# Pump_shield.net
KiCad netlist of a schematic drawn in Altium Designer
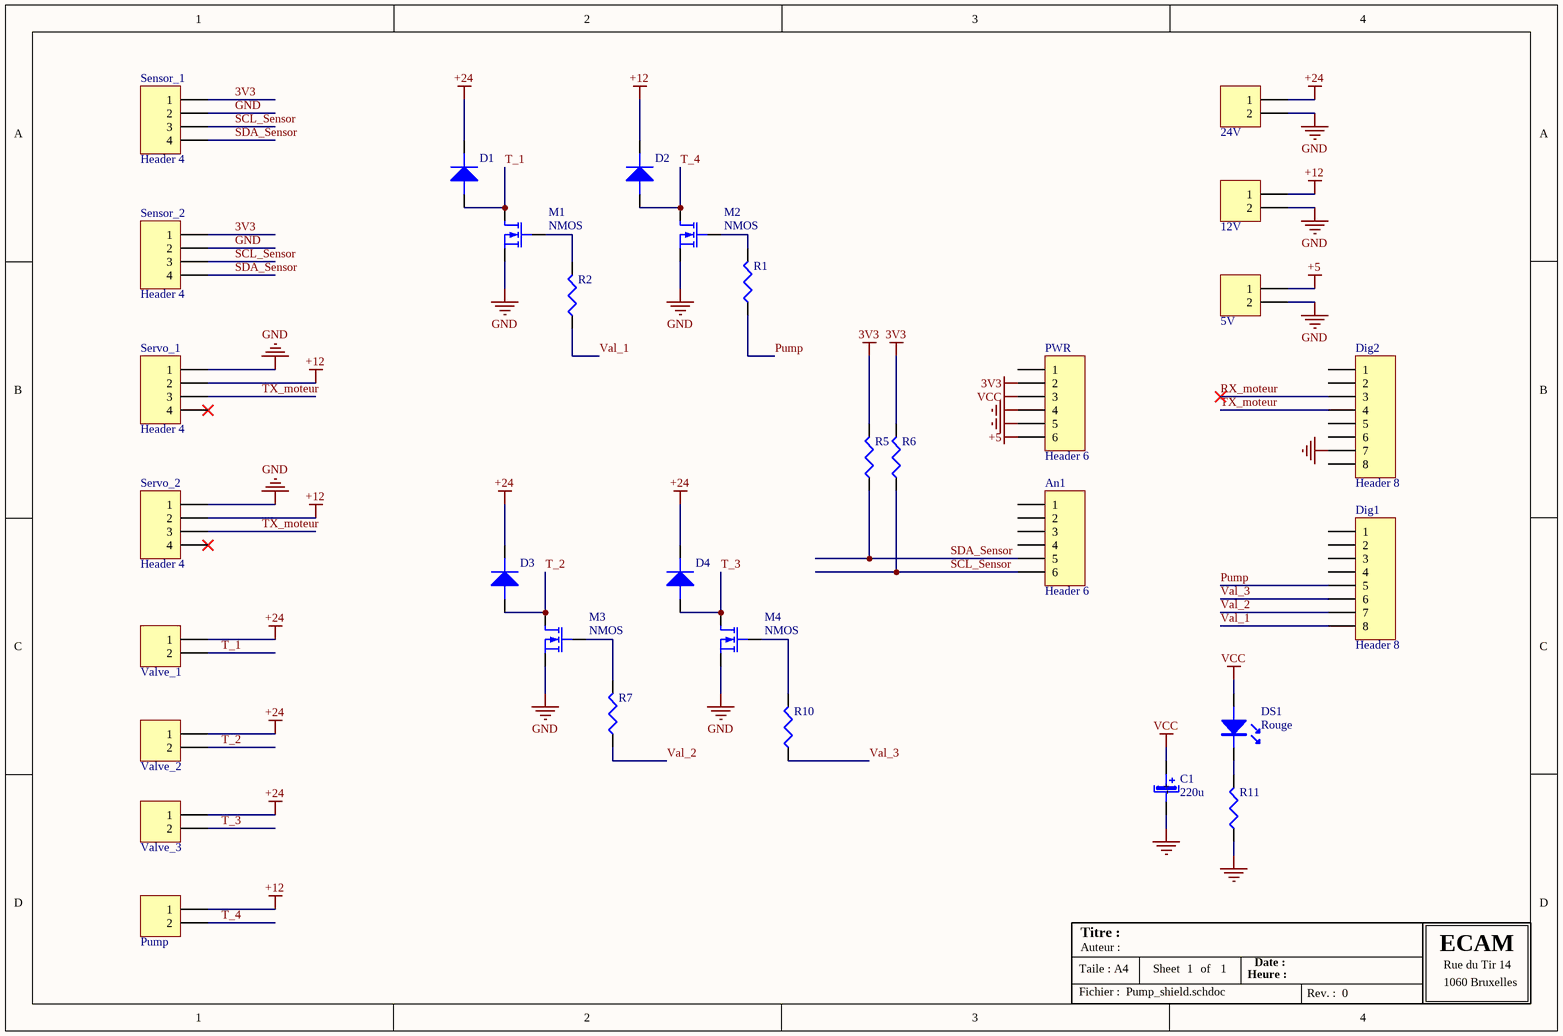
[diagram p0: Pump_shield.schdoc]

(export (version "E")
  (design (tool "Eeschema 10.0.6"))
  (components
    (comp (ref "5V")
      (value "Connecteur 2")
      (footprint "Header_2")
      (description "Header 2")
      (fields (field (name "DESIGNER") "ECAM 2005"))
      (libsource (lib "Eurobot_lib") (part "Connecteur 2"))
    )
    (comp (ref "12V")
      (value "Connecteur 2")
      (footprint "Header_2")
      (description "Header 2")
      (fields (field (name "DESIGNER") "ECAM 2005"))
      (libsource (lib "Eurobot_lib") (part "Connecteur 2"))
    )
    (comp (ref "24V")
      (value "Connecteur 2")
      (footprint "Header_2")
      (description "Header 2")
      (fields (field (name "DESIGNER") "ECAM 2005"))
      (libsource (lib "Eurobot_lib") (part "Connecteur 2"))
    )
    (comp (ref "An1")
      (value "Header 6")
      (footprint "HDR1X6")
      (description "Header, 6-Pin")
      (fields (field (name "PUBLISHER") "Altium Limited"))
      (libsource (lib "Miscellaneous Connectors") (part "Header 6"))
    )
    (comp (ref "C1")
      (value "220u")
      (footprint "CAPAE0810X700N")
      (description "Condensateur polatisé")
      (fields (field (name "Comment") "Cap_220u") (field (name "DESIGNER") "ECAM 2004"))
      (libsource (lib "Eurobot_lib") (part "Cap_220u"))
    )
    (comp (ref "D1")
      (value "Diode")
      (footprint "DIO7.1-3.9x1.9")
      (fields (field (name "DESIGNER") "ECAM 2003"))
      (libsource (lib "Pump_lib") (part "Diode"))
    )
    (comp (ref "D2")
      (value "Diode")
      (footprint "DIO7.1-3.9x1.9")
      (fields (field (name "DESIGNER") "ECAM 2003"))
      (libsource (lib "Pump_lib") (part "Diode"))
    )
    (comp (ref "D3")
      (value "Diode")
      (footprint "DIO7.1-3.9x1.9")
      (fields (field (name "DESIGNER") "ECAM 2003"))
      (libsource (lib "Pump_lib") (part "Diode"))
    )
    (comp (ref "D4")
      (value "Diode")
      (footprint "DIO7.1-3.9x1.9")
      (fields (field (name "DESIGNER") "ECAM 2003"))
      (libsource (lib "Pump_lib") (part "Diode"))
    )
    (comp (ref "Dig1")
      (value "Header 8")
      (footprint "HDR1X8")
      (description "Header, 8-Pin")
      (fields (field (name "PUBLISHER") "Altium Limited"))
      (libsource (lib "Miscellaneous Connectors") (part "Header 8"))
    )
    (comp (ref "Dig2")
      (value "Header 8")
      (footprint "HDR1X8")
      (description "Header, 8-Pin")
      (fields (field (name "PUBLISHER") "Altium Limited"))
      (libsource (lib "Miscellaneous Connectors") (part "Header 8"))
    )
    (comp (ref "DS1")
      (value "LED")
      (footprint "LED 0.1")
      (fields (field (name "COLOR") "Rouge") (field (name "DESIGNER") "ECAM 2004"))
      (libsource (lib "Pump_lib") (part "LED"))
    )
    (comp (ref "M1")
      (value "NMOS")
      (footprint "TO-92bis_MOS-N")
      (description "MOSFET")
      (fields (field (name "Comment") "MOSFET-N") (field (name "DESIGNER") "ECAM 2002"))
      (libsource (lib "Eurobot_lib") (part "MOSFET-N"))
    )
    (comp (ref "M2")
      (value "NMOS")
      (footprint "TO-220_MOS-N")
      (description "MOSFET")
      (fields (field (name "Comment") "MOSFET-N") (field (name "DESIGNER") "ECAM 2002"))
      (libsource (lib "Eurobot_lib") (part "MOSFET-N"))
    )
    (comp (ref "M3")
      (value "NMOS")
      (footprint "TO-92bis_MOS-N")
      (description "MOSFET")
      (fields (field (name "Comment") "MOSFET-N") (field (name "DESIGNER") "ECAM 2002"))
      (libsource (lib "Eurobot_lib") (part "MOSFET-N"))
    )
    (comp (ref "M4")
      (value "NMOS")
      (footprint "TO-92bis_MOS-N")
      (description "MOSFET")
      (fields (field (name "Comment") "MOSFET-N") (field (name "DESIGNER") "ECAM 2002"))
      (libsource (lib "Eurobot_lib") (part "MOSFET-N"))
    )
    (comp (ref "Pump")
      (value "Connecteur 2")
      (footprint "Header_2")
      (description "Header 2")
      (fields (field (name "DESIGNER") "ECAM 2005"))
      (libsource (lib "Eurobot_lib") (part "Connecteur 2"))
    )
    (comp (ref "PWR")
      (value "Header 6")
      (footprint "HDR1X6")
      (description "Header, 6-Pin")
      (fields (field (name "PUBLISHER") "Altium Limited"))
      (libsource (lib "Miscellaneous Connectors") (part "Header 6"))
    )
    (comp (ref "R1")
      (value "Résistance")
      (footprint "AXIAL-0.4")
      (description "Résistance standard")
      (fields (field (name "DESIGNER") "ECAM 2005"))
      (libsource (lib "Pump_lib") (part "Résistance"))
    )
    (comp (ref "R2")
      (value "Résistance")
      (footprint "AXIAL-0.4")
      (description "Résistance standard")
      (fields (field (name "DESIGNER") "ECAM 2005"))
      (libsource (lib "Pump_lib") (part "Résistance"))
    )
    (comp (ref "R5")
      (value "Résistance")
      (footprint "AXIAL-0.4")
      (description "Résistance standard")
      (fields (field (name "DESIGNER") "ECAM 2005"))
      (libsource (lib "Pump_lib") (part "Résistance"))
    )
    (comp (ref "R6")
      (value "Résistance")
      (footprint "AXIAL-0.4")
      (description "Résistance standard")
      (fields (field (name "DESIGNER") "ECAM 2005"))
      (libsource (lib "Pump_lib") (part "Résistance"))
    )
    (comp (ref "R7")
      (value "Résistance")
      (footprint "AXIAL-0.4")
      (description "Résistance standard")
      (fields (field (name "DESIGNER") "ECAM 2005"))
      (libsource (lib "Pump_lib") (part "Résistance"))
    )
    (comp (ref "R10")
      (value "Résistance")
      (footprint "AXIAL-0.4")
      (description "Résistance standard")
      (fields (field (name "DESIGNER") "ECAM 2005"))
      (libsource (lib "Pump_lib") (part "Résistance"))
    )
    (comp (ref "R11")
      (value "Résistance")
      (footprint "AXIAL-0.4")
      (description "Résistance standard")
      (fields (field (name "DESIGNER") "ECAM 2005"))
      (libsource (lib "Pump_lib") (part "Résistance"))
    )
    (comp (ref "Sensor_1")
      (value "Header 4")
      (footprint "Header_4")
      (description "Header, 4-Pin")
      (fields (field (name "PUBLISHER") "Altium Limited"))
      (libsource (lib "Eurobot_lib") (part "Header 4"))
    )
    (comp (ref "Sensor_2")
      (value "Header 4")
      (footprint "Header_4")
      (description "Header, 4-Pin")
      (fields (field (name "PUBLISHER") "Altium Limited"))
      (libsource (lib "Eurobot_lib") (part "Header 4"))
    )
    (comp (ref "Servo_1")
      (value "Header 4")
      (footprint "Header_4")
      (description "Header, 4-Pin")
      (fields (field (name "PUBLISHER") "Altium Limited"))
      (libsource (lib "Eurobot_lib") (part "Header 4"))
    )
    (comp (ref "Servo_2")
      (value "Header 4")
      (footprint "Header_4")
      (description "Header, 4-Pin")
      (fields (field (name "PUBLISHER") "Altium Limited"))
      (libsource (lib "Eurobot_lib") (part "Header 4"))
    )
    (comp (ref "Valve_1")
      (value "Connecteur 2")
      (footprint "Header_2")
      (description "Header 2")
      (fields (field (name "DESIGNER") "ECAM 2005"))
      (libsource (lib "Eurobot_lib") (part "Connecteur 2"))
    )
    (comp (ref "Valve_2")
      (value "Connecteur 2")
      (footprint "Header_2")
      (description "Header 2")
      (fields (field (name "DESIGNER") "ECAM 2005"))
      (libsource (lib "Eurobot_lib") (part "Connecteur 2"))
    )
    (comp (ref "Valve_3")
      (value "Connecteur 2")
      (footprint "Header_2")
      (description "Header 2")
      (fields (field (name "DESIGNER") "ECAM 2005"))
      (libsource (lib "Eurobot_lib") (part "Connecteur 2"))
    )
  )
  (nets
    (net (code "1") (name "+5") (class "Default")
      (node (ref "5V") (pin "1") (pinfunction "1_1") (pintype "passive"))
      (node (ref "PWR") (pin "6") (pinfunction "6_6") (pintype "passive"))
    )
    (net (code "2") (name "+12") (class "Default")
      (node (ref "12V") (pin "1") (pinfunction "1_1") (pintype "passive"))
      (node (ref "D2") (pin "2") (pinfunction "K_2") (pintype "passive"))
      (node (ref "Pump") (pin "1") (pinfunction "1_1") (pintype "passive"))
      (node (ref "Servo_1") (pin "2") (pinfunction "2_2") (pintype "passive"))
      (node (ref "Servo_2") (pin "2") (pinfunction "2_2") (pintype "passive"))
    )
    (net (code "3") (name "+24") (class "Default")
      (node (ref "24V") (pin "1") (pinfunction "1_1") (pintype "passive"))
      (node (ref "D1") (pin "2") (pinfunction "K_2") (pintype "passive"))
      (node (ref "D3") (pin "2") (pinfunction "K_2") (pintype "passive"))
      (node (ref "D4") (pin "2") (pinfunction "K_2") (pintype "passive"))
      (node (ref "Valve_1") (pin "1") (pinfunction "1_1") (pintype "passive"))
      (node (ref "Valve_2") (pin "1") (pinfunction "1_1") (pintype "passive"))
      (node (ref "Valve_3") (pin "1") (pinfunction "1_1") (pintype "passive"))
    )
    (net (code "4") (name "/Pump") (class "Default")
      (node (ref "Dig1") (pin "5") (pinfunction "5_5") (pintype "passive"))
      (node (ref "R1") (pin "1") (pinfunction "1_1") (pintype "passive"))
    )
    (net (code "5") (name "/RX_moteur") (class "Default")
      (node (ref "Dig2") (pin "3") (pinfunction "3_3") (pintype "passive+no_connect"))
    )
    (net (code "6") (name "/SCL_Sensor") (class "Default")
      (node (ref "An1") (pin "6") (pinfunction "6_6") (pintype "passive"))
      (node (ref "R6") (pin "1") (pinfunction "1_1") (pintype "passive"))
      (node (ref "Sensor_1") (pin "3") (pinfunction "3_3") (pintype "passive"))
      (node (ref "Sensor_2") (pin "3") (pinfunction "3_3") (pintype "passive"))
    )
    (net (code "7") (name "/SDA_Sensor") (class "Default")
      (node (ref "An1") (pin "5") (pinfunction "5_5") (pintype "passive"))
      (node (ref "R5") (pin "1") (pinfunction "1_1") (pintype "passive"))
      (node (ref "Sensor_1") (pin "4") (pinfunction "4_4") (pintype "passive"))
      (node (ref "Sensor_2") (pin "4") (pinfunction "4_4") (pintype "passive"))
    )
    (net (code "8") (name "/TX_moteur") (class "Default")
      (node (ref "Dig2") (pin "4") (pinfunction "4_4") (pintype "passive"))
      (node (ref "Servo_1") (pin "3") (pinfunction "3_3") (pintype "passive"))
      (node (ref "Servo_2") (pin "3") (pinfunction "3_3") (pintype "passive"))
    )
    (net (code "9") (name "/T_1") (class "Default")
      (node (ref "D1") (pin "1") (pinfunction "A_1") (pintype "passive"))
      (node (ref "M1") (pin "D") (pinfunction "D_D") (pintype "passive"))
      (node (ref "Valve_1") (pin "2") (pinfunction "2_2") (pintype "passive"))
    )
    (net (code "10") (name "/T_2") (class "Default")
      (node (ref "D3") (pin "1") (pinfunction "A_1") (pintype "passive"))
      (node (ref "M3") (pin "D") (pinfunction "D_D") (pintype "passive"))
      (node (ref "Valve_2") (pin "2") (pinfunction "2_2") (pintype "passive"))
    )
    (net (code "11") (name "/T_3") (class "Default")
      (node (ref "D4") (pin "1") (pinfunction "A_1") (pintype "passive"))
      (node (ref "M4") (pin "D") (pinfunction "D_D") (pintype "passive"))
      (node (ref "Valve_3") (pin "2") (pinfunction "2_2") (pintype "passive"))
    )
    (net (code "12") (name "/T_4") (class "Default")
      (node (ref "D2") (pin "1") (pinfunction "A_1") (pintype "passive"))
      (node (ref "M2") (pin "D") (pinfunction "D_D") (pintype "passive"))
      (node (ref "Pump") (pin "2") (pinfunction "2_2") (pintype "passive"))
    )
    (net (code "13") (name "/Val_1") (class "Default")
      (node (ref "Dig1") (pin "8") (pinfunction "8_8") (pintype "passive"))
      (node (ref "R2") (pin "1") (pinfunction "1_1") (pintype "passive"))
    )
    (net (code "14") (name "/Val_2") (class "Default")
      (node (ref "Dig1") (pin "7") (pinfunction "7_7") (pintype "passive"))
      (node (ref "R7") (pin "1") (pinfunction "1_1") (pintype "passive"))
    )
    (net (code "15") (name "/Val_3") (class "Default")
      (node (ref "Dig1") (pin "6") (pinfunction "6_6") (pintype "passive"))
      (node (ref "R10") (pin "1") (pinfunction "1_1") (pintype "passive"))
    )
    (net (code "16") (name "3V3") (class "Default")
      (node (ref "PWR") (pin "2") (pinfunction "2_2") (pintype "passive"))
      (node (ref "R5") (pin "2") (pinfunction "2_2") (pintype "passive"))
      (node (ref "R6") (pin "2") (pinfunction "2_2") (pintype "passive"))
      (node (ref "Sensor_1") (pin "1") (pinfunction "1_1") (pintype "passive"))
      (node (ref "Sensor_2") (pin "1") (pinfunction "1_1") (pintype "passive"))
    )
    (net (code "17") (name "GND") (class "Default")
      (node (ref "12V") (pin "2") (pinfunction "2_2") (pintype "passive"))
      (node (ref "24V") (pin "2") (pinfunction "2_2") (pintype "passive"))
      (node (ref "5V") (pin "2") (pinfunction "2_2") (pintype "passive"))
      (node (ref "C1") (pin "NEG") (pinfunction "-_NEG") (pintype "passive"))
      (node (ref "Dig2") (pin "7") (pinfunction "7_7") (pintype "passive"))
      (node (ref "M1") (pin "S") (pinfunction "S_S") (pintype "passive"))
      (node (ref "M2") (pin "S") (pinfunction "S_S") (pintype "passive"))
      (node (ref "M3") (pin "S") (pinfunction "S_S") (pintype "passive"))
      (node (ref "M4") (pin "S") (pinfunction "S_S") (pintype "passive"))
      (node (ref "PWR") (pin "4") (pinfunction "4_4") (pintype "passive"))
      (node (ref "PWR") (pin "5") (pinfunction "5_5") (pintype "passive"))
      (node (ref "R11") (pin "1") (pinfunction "1_1") (pintype "passive"))
      (node (ref "Sensor_1") (pin "2") (pinfunction "2_2") (pintype "passive"))
      (node (ref "Sensor_2") (pin "2") (pinfunction "2_2") (pintype "passive"))
      (node (ref "Servo_1") (pin "1") (pinfunction "1_1") (pintype "passive"))
      (node (ref "Servo_2") (pin "1") (pinfunction "1_1") (pintype "passive"))
    )
    (net (code "18") (name "Net-(DS1-K)") (class "Default")
      (node (ref "DS1") (pin "2") (pinfunction "K_2") (pintype "passive"))
      (node (ref "R11") (pin "2") (pinfunction "2_2") (pintype "passive"))
    )
    (net (code "19") (name "Net-(M1-PadG)") (class "Default")
      (node (ref "M1") (pin "G") (pinfunction "G_G") (pintype "passive"))
      (node (ref "R2") (pin "2") (pinfunction "2_2") (pintype "passive"))
    )
    (net (code "20") (name "Net-(M2-PadG)") (class "Default")
      (node (ref "M2") (pin "G") (pinfunction "G_G") (pintype "passive"))
      (node (ref "R1") (pin "2") (pinfunction "2_2") (pintype "passive"))
    )
    (net (code "21") (name "Net-(M3-PadG)") (class "Default")
      (node (ref "M3") (pin "G") (pinfunction "G_G") (pintype "passive"))
      (node (ref "R7") (pin "2") (pinfunction "2_2") (pintype "passive"))
    )
    (net (code "22") (name "Net-(M4-PadG)") (class "Default")
      (node (ref "M4") (pin "G") (pinfunction "G_G") (pintype "passive"))
      (node (ref "R10") (pin "2") (pinfunction "2_2") (pintype "passive"))
    )
    (net (code "23") (name "VCC") (class "Default")
      (node (ref "C1") (pin "POS") (pinfunction "+_POS") (pintype "passive"))
      (node (ref "DS1") (pin "1") (pinfunction "A_1") (pintype "passive"))
      (node (ref "PWR") (pin "3") (pinfunction "3_3") (pintype "passive"))
    )
    (net (code "24") (name "unconnected-(An1-Pad1)") (class "Default")
      (node (ref "An1") (pin "1") (pinfunction "1_1") (pintype "passive"))
    )
    (net (code "25") (name "unconnected-(An1-Pad2)") (class "Default")
      (node (ref "An1") (pin "2") (pinfunction "2_2") (pintype "passive"))
    )
    (net (code "26") (name "unconnected-(An1-Pad3)") (class "Default")
      (node (ref "An1") (pin "3") (pinfunction "3_3") (pintype "passive"))
    )
    (net (code "27") (name "unconnected-(An1-Pad4)") (class "Default")
      (node (ref "An1") (pin "4") (pinfunction "4_4") (pintype "passive"))
    )
    (net (code "28") (name "unconnected-(Dig1-Pad1)") (class "Default")
      (node (ref "Dig1") (pin "1") (pinfunction "1_1") (pintype "passive"))
    )
    (net (code "29") (name "unconnected-(Dig1-Pad2)") (class "Default")
      (node (ref "Dig1") (pin "2") (pinfunction "2_2") (pintype "passive"))
    )
    (net (code "30") (name "unconnected-(Dig1-Pad3)") (class "Default")
      (node (ref "Dig1") (pin "3") (pinfunction "3_3") (pintype "passive"))
    )
    (net (code "31") (name "unconnected-(Dig1-Pad4)") (class "Default")
      (node (ref "Dig1") (pin "4") (pinfunction "4_4") (pintype "passive"))
    )
    (net (code "32") (name "unconnected-(Dig2-Pad1)") (class "Default")
      (node (ref "Dig2") (pin "1") (pinfunction "1_1") (pintype "passive"))
    )
    (net (code "33") (name "unconnected-(Dig2-Pad2)") (class "Default")
      (node (ref "Dig2") (pin "2") (pinfunction "2_2") (pintype "passive"))
    )
    (net (code "34") (name "unconnected-(Dig2-Pad5)") (class "Default")
      (node (ref "Dig2") (pin "5") (pinfunction "5_5") (pintype "passive"))
    )
    (net (code "35") (name "unconnected-(Dig2-Pad6)") (class "Default")
      (node (ref "Dig2") (pin "6") (pinfunction "6_6") (pintype "passive"))
    )
    (net (code "36") (name "unconnected-(Dig2-Pad8)") (class "Default")
      (node (ref "Dig2") (pin "8") (pinfunction "8_8") (pintype "passive"))
    )
    (net (code "37") (name "unconnected-(PWR-Pad1)") (class "Default")
      (node (ref "PWR") (pin "1") (pinfunction "1_1") (pintype "passive"))
    )
    (net (code "38") (name "unconnected-(Servo_1-Pad4)") (class "Default")
      (node (ref "Servo_1") (pin "4") (pinfunction "4_4") (pintype "passive+no_connect"))
    )
    (net (code "39") (name "unconnected-(Servo_2-Pad4)") (class "Default")
      (node (ref "Servo_2") (pin "4") (pinfunction "4_4") (pintype "passive+no_connect"))
    )
  )
)
